# Power.net
KiCad netlist of a schematic drawn in Altium Designer
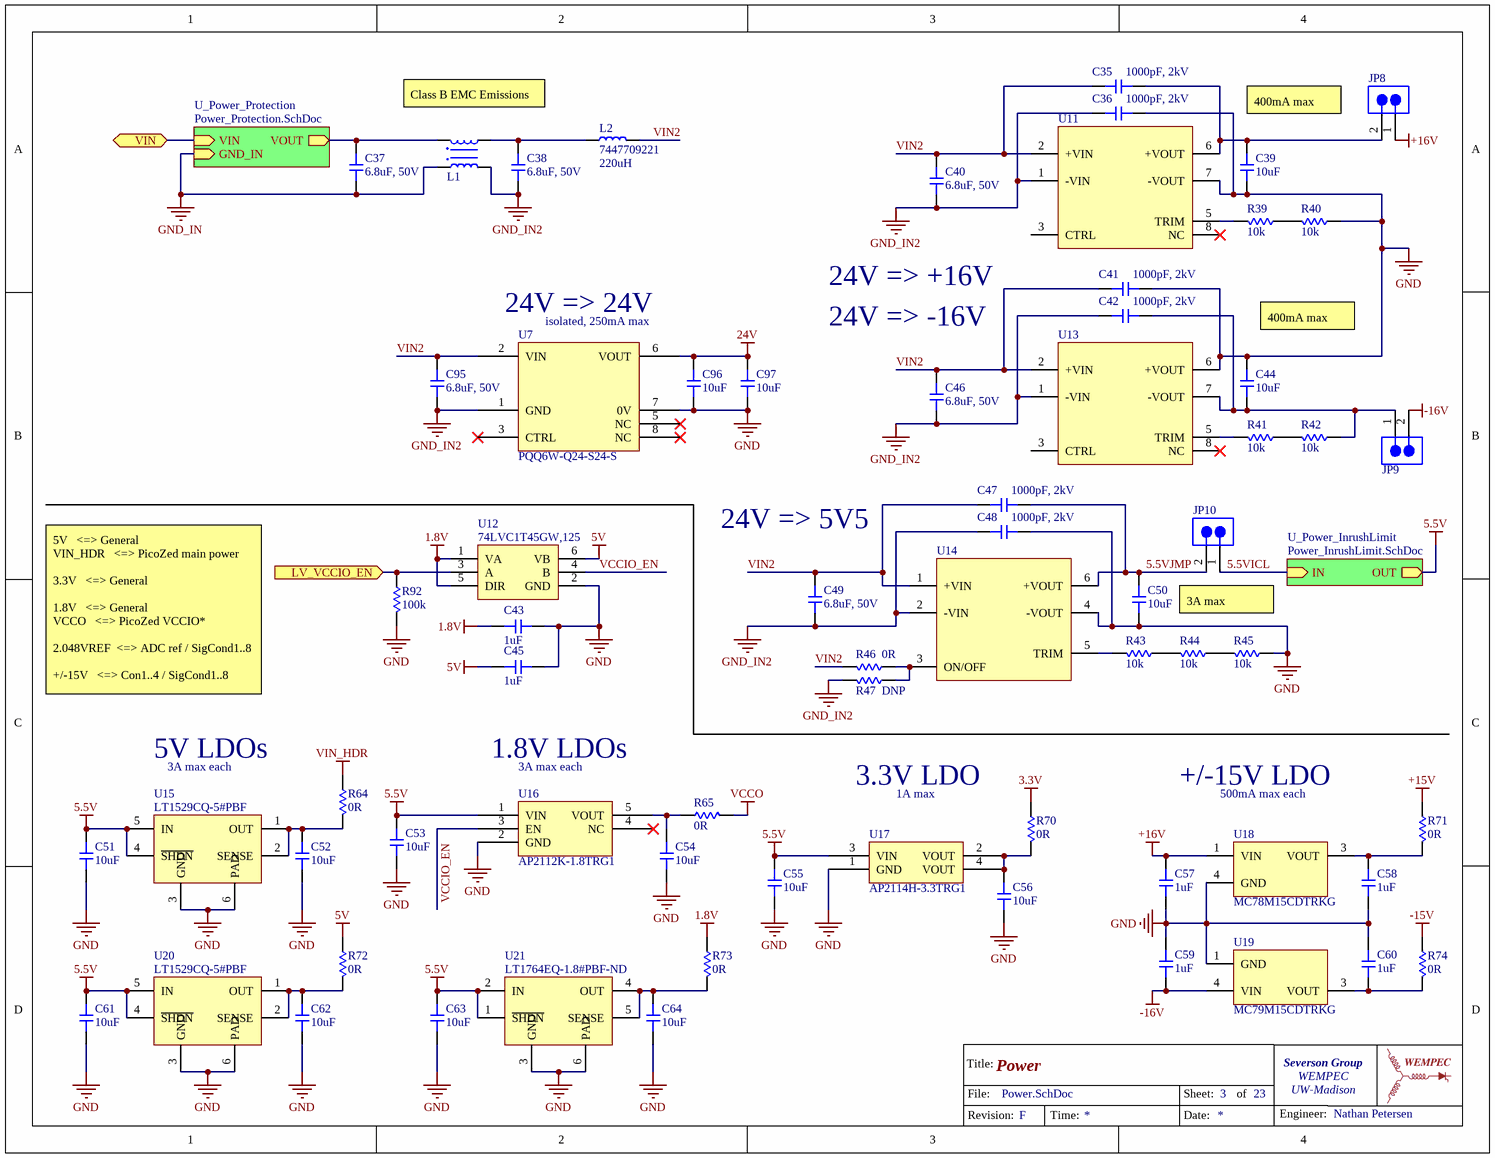
[diagram p0: Power.SchDoc]

(export (version "E")
  (design (tool "Eeschema 10.0.6"))
  (components
    (comp (ref "C35")
      (value "1000pF, 2kV")
      (footprint "1808-CAP")
      (description "Capacitor")
      (libsource (lib "AMDC") (part "Capacitor"))
    )
    (comp (ref "C36")
      (value "1000pF, 2kV")
      (footprint "1808-CAP")
      (description "Capacitor")
      (libsource (lib "AMDC") (part "Capacitor"))
    )
    (comp (ref "C37")
      (value "6.8uF, 50V")
      (footprint "1812-CAP")
      (description "Capacitor")
      (libsource (lib "AMDC") (part "Capacitor"))
    )
    (comp (ref "C38")
      (value "6.8uF, 50V")
      (footprint "1812-CAP")
      (description "Capacitor")
      (libsource (lib "AMDC") (part "Capacitor"))
    )
    (comp (ref "C39")
      (value "10uF")
      (footprint "0603-CAP")
      (description "Capacitor")
      (libsource (lib "AMDC") (part "Capacitor"))
    )
    (comp (ref "C40")
      (value "6.8uF, 50V")
      (footprint "1812-CAP")
      (description "Capacitor")
      (libsource (lib "AMDC") (part "Capacitor"))
    )
    (comp (ref "C41")
      (value "1000pF, 2kV")
      (footprint "1808-CAP")
      (description "Capacitor")
      (libsource (lib "AMDC") (part "Capacitor"))
    )
    (comp (ref "C42")
      (value "1000pF, 2kV")
      (footprint "1808-CAP")
      (description "Capacitor")
      (libsource (lib "AMDC") (part "Capacitor"))
    )
    (comp (ref "C43")
      (value "1uF")
      (footprint "0603-CAP")
      (description "Capacitor")
      (libsource (lib "AMDC") (part "Capacitor"))
    )
    (comp (ref "C44")
      (value "10uF")
      (footprint "0603-CAP")
      (description "Capacitor")
      (libsource (lib "AMDC") (part "Capacitor"))
    )
    (comp (ref "C45")
      (value "1uF")
      (footprint "0603-CAP")
      (description "Capacitor")
      (libsource (lib "AMDC") (part "Capacitor"))
    )
    (comp (ref "C46")
      (value "6.8uF, 50V")
      (footprint "1812-CAP")
      (description "Capacitor")
      (libsource (lib "AMDC") (part "Capacitor"))
    )
    (comp (ref "C47")
      (value "1000pF, 2kV")
      (footprint "1808-CAP")
      (description "Capacitor")
      (libsource (lib "AMDC") (part "Capacitor"))
    )
    (comp (ref "C48")
      (value "1000pF, 2kV")
      (footprint "1808-CAP")
      (description "Capacitor")
      (libsource (lib "AMDC") (part "Capacitor"))
    )
    (comp (ref "C49")
      (value "6.8uF, 50V")
      (footprint "1812-CAP")
      (description "Capacitor")
      (libsource (lib "AMDC") (part "Capacitor"))
    )
    (comp (ref "C50")
      (value "10uF")
      (footprint "0603-CAP")
      (description "Capacitor")
      (libsource (lib "AMDC") (part "Capacitor"))
    )
    (comp (ref "C51")
      (value "10uF")
      (footprint "0603-CAP")
      (description "Capacitor")
      (libsource (lib "AMDC") (part "Capacitor"))
    )
    (comp (ref "C52")
      (value "10uF")
      (footprint "0603-CAP")
      (description "Capacitor")
      (libsource (lib "AMDC") (part "Capacitor"))
    )
    (comp (ref "C53")
      (value "10uF")
      (footprint "0603-CAP")
      (description "Capacitor")
      (libsource (lib "AMDC") (part "Capacitor"))
    )
    (comp (ref "C54")
      (value "10uF")
      (footprint "0603-CAP")
      (description "Capacitor")
      (libsource (lib "AMDC") (part "Capacitor"))
    )
    (comp (ref "C55")
      (value "10uF")
      (footprint "0603-CAP")
      (description "Capacitor")
      (libsource (lib "AMDC") (part "Capacitor"))
    )
    (comp (ref "C56")
      (value "10uF")
      (footprint "0603-CAP")
      (description "Capacitor")
      (libsource (lib "AMDC") (part "Capacitor"))
    )
    (comp (ref "C57")
      (value "1uF")
      (footprint "0603-CAP")
      (description "Capacitor")
      (libsource (lib "AMDC") (part "Capacitor"))
    )
    (comp (ref "C58")
      (value "1uF")
      (footprint "0603-CAP")
      (description "Capacitor")
      (libsource (lib "AMDC") (part "Capacitor"))
    )
    (comp (ref "C59")
      (value "1uF")
      (footprint "0603-CAP")
      (description "Capacitor")
      (libsource (lib "AMDC") (part "Capacitor"))
    )
    (comp (ref "C60")
      (value "1uF")
      (footprint "0603-CAP")
      (description "Capacitor")
      (libsource (lib "AMDC") (part "Capacitor"))
    )
    (comp (ref "C61")
      (value "10uF")
      (footprint "0603-CAP")
      (description "Capacitor")
      (libsource (lib "AMDC") (part "Capacitor"))
    )
    (comp (ref "C62")
      (value "10uF")
      (footprint "0603-CAP")
      (description "Capacitor")
      (libsource (lib "AMDC") (part "Capacitor"))
    )
    (comp (ref "C63")
      (value "10uF")
      (footprint "0603-CAP")
      (description "Capacitor")
      (libsource (lib "AMDC") (part "Capacitor"))
    )
    (comp (ref "C64")
      (value "10uF")
      (footprint "0603-CAP")
      (description "Capacitor")
      (libsource (lib "AMDC") (part "Capacitor"))
    )
    (comp (ref "C95")
      (value "6.8uF, 50V")
      (footprint "1812-CAP")
      (description "Capacitor")
      (libsource (lib "AMDC") (part "Capacitor"))
    )
    (comp (ref "C96")
      (value "10uF")
      (footprint "0603-CAP")
      (description "Capacitor")
      (libsource (lib "AMDC") (part "Capacitor"))
    )
    (comp (ref "C97")
      (value "10uF")
      (footprint "0603-CAP")
      (description "Capacitor")
      (libsource (lib "AMDC") (part "Capacitor"))
    )
    (comp (ref "JP8")
      (value "Jumper2")
      (footprint "PIN_HEADER_1x2")
      (libsource (lib "AMDC") (part "Jumper2"))
    )
    (comp (ref "JP9")
      (value "Jumper2")
      (footprint "PIN_HEADER_1x2")
      (libsource (lib "AMDC") (part "Jumper2"))
    )
    (comp (ref "JP10")
      (value "Jumper2")
      (footprint "PIN_HEADER_1x2")
      (libsource (lib "AMDC") (part "Jumper2"))
    )
    (comp (ref "L1")
      (value "CMC  744273801")
      (footprint "CMC 744273801")
      (description "CMC 450UH 6.5A 2LN TH")
      (libsource (lib "AMDC") (part "CMC  744273801"))
    )
    (comp (ref "L2")
      (value "7447709221")
      (footprint "7447709221")
      (description "FIXED IND 220UH 1.8A 300 MOHM")
      (fields (field (name "ALTIUM_VALUE") "220uH"))
      (libsource (lib "AMDC") (part "7447709221"))
    )
    (comp (ref "R39")
      (value "10k")
      (footprint "0603-RES")
      (description "Resistor")
      (libsource (lib "AMDC") (part "Resistor"))
    )
    (comp (ref "R40")
      (value "10k")
      (footprint "0603-RES")
      (description "Resistor")
      (libsource (lib "AMDC") (part "Resistor"))
    )
    (comp (ref "R41")
      (value "10k")
      (footprint "0603-RES")
      (description "Resistor")
      (libsource (lib "AMDC") (part "Resistor"))
    )
    (comp (ref "R42")
      (value "10k")
      (footprint "0603-RES")
      (description "Resistor")
      (libsource (lib "AMDC") (part "Resistor"))
    )
    (comp (ref "R43")
      (value "10k")
      (footprint "0603-RES")
      (description "Resistor")
      (libsource (lib "AMDC") (part "Resistor"))
    )
    (comp (ref "R44")
      (value "10k")
      (footprint "0603-RES")
      (description "Resistor")
      (libsource (lib "AMDC") (part "Resistor"))
    )
    (comp (ref "R45")
      (value "10k")
      (footprint "0603-RES")
      (description "Resistor")
      (libsource (lib "AMDC") (part "Resistor"))
    )
    (comp (ref "R46")
      (value "0R")
      (footprint "1206-RES")
      (description "Resistor")
      (libsource (lib "AMDC") (part "Resistor"))
    )
    (comp (ref "R47")
      (value "DNP")
      (footprint "1206-RES")
      (description "Resistor")
      (libsource (lib "AMDC") (part "Resistor"))
    )
    (comp (ref "R64")
      (value "0R")
      (footprint "1206-RES")
      (description "Resistor")
      (libsource (lib "AMDC") (part "Resistor"))
    )
    (comp (ref "R65")
      (value "0R")
      (footprint "1206-RES")
      (description "Resistor")
      (libsource (lib "AMDC") (part "Resistor"))
    )
    (comp (ref "R70")
      (value "0R")
      (footprint "1206-RES")
      (description "Resistor")
      (libsource (lib "AMDC") (part "Resistor"))
    )
    (comp (ref "R71")
      (value "0R")
      (footprint "1206-RES")
      (description "Resistor")
      (libsource (lib "AMDC") (part "Resistor"))
    )
    (comp (ref "R72")
      (value "0R")
      (footprint "1206-RES")
      (description "Resistor")
      (libsource (lib "AMDC") (part "Resistor"))
    )
    (comp (ref "R73")
      (value "0R")
      (footprint "1206-RES")
      (description "Resistor")
      (libsource (lib "AMDC") (part "Resistor"))
    )
    (comp (ref "R74")
      (value "0R")
      (footprint "1206-RES")
      (description "Resistor")
      (libsource (lib "AMDC") (part "Resistor"))
    )
    (comp (ref "R92")
      (value "100k")
      (footprint "0603-RES")
      (description "Resistor")
      (libsource (lib "AMDC") (part "Resistor"))
    )
    (comp (ref "U7")
      (value "PQQ6W-Q24-S24-S")
      (footprint "PQQ6W-Q24-S24-S")
      (description "DC-DC ISOLATED, 6 W, 9~36 VDC IN")
      (libsource (lib "AMDC") (part "PQQ6W-Q24-S24-S"))
    )
    (comp (ref "U11")
      (value "DCDC Converter RS6")
      (footprint "RS6 DCDC")
      (description "Recom RS6")
      (libsource (lib "AMDC") (part "DCDC Converter RS6"))
    )
    (comp (ref "U12")
      (value "74LVC1T45GW,125")
      (footprint "SOT65P210X110-6N")
      (description "TXRX XLATING DUAL 3ST 6TSSOP")
      (libsource (lib "AMDC") (part "74LVC1T45GW,125"))
    )
    (comp (ref "U13")
      (value "DCDC Converter RS6")
      (footprint "RS6 DCDC")
      (description "Recom RS6")
      (libsource (lib "AMDC") (part "DCDC Converter RS6"))
    )
    (comp (ref "U14")
      (value "SHHD003A0A4Z")
      (footprint "DCDC SHHD003A0A41-SRZ")
      (description "DC DC CONVERTER 5V 15W")
      (libsource (lib "AMDC") (part "DCDC Converter SHHD003A0A41Z"))
    )
    (comp (ref "U15")
      (value "LT1529CQ-5#PBF")
      (footprint "5-DDPAK")
      (description "IC REG LINEAR 5V 3A 5DDPAK")
      (libsource (lib "AMDC") (part "LT1529CQ-5#PBF"))
    )
    (comp (ref "U16")
      (value "AP2112K-1.8TRG1")
      (footprint "SOT95P280X145-5N")
      (description "IC REG LINEAR 1.8V 600MA SOT25")
      (libsource (lib "AMDC") (part "AP2112K-1.8TRG1"))
    )
    (comp (ref "U17")
      (value "AP2114H-3.3TRG1")
      (footprint "SOT230P700X180-4N")
      (description "IC REG LINEAR 3.3V 1A SOT223")
      (libsource (lib "AMDC") (part "AP2114H-3.3TRG1"))
    )
    (comp (ref "U18")
      (value "MC78M15CDTRKG")
      (footprint "DPAK229P991X238-3N")
      (description "IC REG LINEAR 15V 500MA DPAK")
      (libsource (lib "AMDC") (part "MC78M15CDTRKG"))
    )
    (comp (ref "U19")
      (value "MC79M15CDTRKG")
      (footprint "DPAK229P991X238-3N")
      (description "IC REG LINEAR -15V 500MA DPAK")
      (libsource (lib "AMDC") (part "MC79M15CDTRKG"))
    )
    (comp (ref "U20")
      (value "LT1529CQ-5#PBF")
      (footprint "5-DDPAK")
      (description "IC REG LINEAR 5V 3A 5DDPAK")
      (libsource (lib "AMDC") (part "LT1529CQ-5#PBF"))
    )
    (comp (ref "U21")
      (value "LT1764EQ-1.8#PBF-ND")
      (footprint "5-DDPAK")
      (description "IC REG LINEAR 1.8V 3A 5DDPAK")
      (libsource (lib "AMDC") (part "LT1764EQ-1.8#PBF-ND"))
    )
  )
  (nets
    (net (code "1") (name "+15V") (class "Default")
      (node (ref "R71") (pin "1") (pinfunction "1_1") (pintype "passive"))
    )
    (net (code "2") (name "+16V") (class "Default")
      (node (ref "C57") (pin "2") (pinfunction "2_2") (pintype "passive"))
      (node (ref "JP8") (pin "1") (pinfunction "76_1") (pintype "passive"))
      (node (ref "U18") (pin "1") (pinfunction "VIN_1") (pintype "passive"))
    )
    (net (code "3") (name "-15V") (class "Default")
      (node (ref "R74") (pin "1") (pinfunction "1_1") (pintype "passive"))
    )
    (net (code "4") (name "-16V") (class "Default")
      (node (ref "C59") (pin "1") (pinfunction "1_1") (pintype "passive"))
      (node (ref "JP9") (pin "2") (pinfunction "75_2") (pintype "passive"))
      (node (ref "U19") (pin "4") (pinfunction "VIN_4") (pintype "passive"))
    )
    (net (code "5") (name "/5.5VICL") (class "Default")
      (node (ref "JP10") (pin "1") (pinfunction "76_1") (pintype "passive"))
    )
    (net (code "6") (name "/5.5VJMP") (class "Default")
      (node (ref "C47") (pin "2") (pinfunction "2_2") (pintype "passive"))
      (node (ref "C50") (pin "2") (pinfunction "2_2") (pintype "passive"))
      (node (ref "JP10") (pin "2") (pinfunction "75_2") (pintype "passive"))
      (node (ref "U14") (pin "6") (pinfunction "+VOUT_6") (pintype "passive"))
    )
    (net (code "7") (name "/LV_VCCIO_EN") (class "Default")
      (node (ref "R92") (pin "1") (pinfunction "1_1") (pintype "passive"))
      (node (ref "U12") (pin "3") (pinfunction "A_3") (pintype "passive"))
    )
    (net (code "8") (name "/VCCIO_EN") (class "Default")
      (node (ref "U12") (pin "4") (pinfunction "B_4") (pintype "passive"))
      (node (ref "U16") (pin "3") (pinfunction "EN_3") (pintype "passive"))
    )
    (net (code "10") (name "/VIN2") (class "Default")
      (node (ref "C35") (pin "1") (pinfunction "1_1") (pintype "passive"))
      (node (ref "C40") (pin "2") (pinfunction "2_2") (pintype "passive"))
      (node (ref "C41") (pin "1") (pinfunction "1_1") (pintype "passive"))
      (node (ref "C46") (pin "2") (pinfunction "2_2") (pintype "passive"))
      (node (ref "C47") (pin "1") (pinfunction "1_1") (pintype "passive"))
      (node (ref "C49") (pin "2") (pinfunction "2_2") (pintype "passive"))
      (node (ref "C95") (pin "2") (pinfunction "2_2") (pintype "passive"))
      (node (ref "L2") (pin "1") (pinfunction "1_1") (pintype "passive"))
      (node (ref "R46") (pin "2") (pinfunction "2_2") (pintype "passive"))
      (node (ref "U11") (pin "2") (pinfunction "+VIN_2") (pintype "passive"))
      (node (ref "U13") (pin "2") (pinfunction "+VIN_2") (pintype "passive"))
      (node (ref "U14") (pin "1") (pinfunction "+VIN_1") (pintype "passive"))
      (node (ref "U7") (pin "2") (pinfunction "VIN_2") (pintype "passive"))
    )
    (net (code "11") (name "/VOUT") (class "Default")
      (node (ref "C37") (pin "2") (pinfunction "2_2") (pintype "passive"))
      (node (ref "L1") (pin "1") (pinfunction "1_1") (pintype "passive"))
    )
    (net (code "12") (name "1.8V") (class "Default")
      (node (ref "C43") (pin "1") (pinfunction "1_1") (pintype "passive"))
      (node (ref "R73") (pin "1") (pinfunction "1_1") (pintype "passive"))
      (node (ref "U12") (pin "1") (pinfunction "VA_1") (pintype "passive"))
      (node (ref "U12") (pin "5") (pinfunction "DIR_5") (pintype "passive"))
    )
    (net (code "13") (name "3.3V") (class "Default")
      (node (ref "R70") (pin "1") (pinfunction "1_1") (pintype "passive"))
    )
    (net (code "14") (name "5.5V") (class "Default")
      (node (ref "C51") (pin "1") (pinfunction "1_1") (pintype "passive"))
      (node (ref "C53") (pin "1") (pinfunction "1_1") (pintype "passive"))
      (node (ref "C55") (pin "1") (pinfunction "1_1") (pintype "passive"))
      (node (ref "C61") (pin "1") (pinfunction "1_1") (pintype "passive"))
      (node (ref "C63") (pin "1") (pinfunction "1_1") (pintype "passive"))
      (node (ref "U15") (pin "4") (pinfunction "~{SHDN}_4") (pintype "passive"))
      (node (ref "U15") (pin "5") (pinfunction "IN_5") (pintype "passive"))
      (node (ref "U16") (pin "1") (pinfunction "VIN_1") (pintype "passive"))
      (node (ref "U17") (pin "3") (pinfunction "VIN_3") (pintype "passive"))
      (node (ref "U20") (pin "4") (pinfunction "~{SHDN}_4") (pintype "passive"))
      (node (ref "U20") (pin "5") (pinfunction "IN_5") (pintype "passive"))
      (node (ref "U21") (pin "1") (pinfunction "~{SHDN}_1") (pintype "passive"))
      (node (ref "U21") (pin "2") (pinfunction "IN_2") (pintype "passive"))
    )
    (net (code "15") (name "5V") (class "Default")
      (node (ref "C45") (pin "1") (pinfunction "1_1") (pintype "passive"))
      (node (ref "R72") (pin "1") (pinfunction "1_1") (pintype "passive"))
      (node (ref "U12") (pin "6") (pinfunction "VB_6") (pintype "passive"))
    )
    (net (code "16") (name "24V") (class "Default")
      (node (ref "C96") (pin "2") (pinfunction "2_2") (pintype "passive"))
      (node (ref "C97") (pin "2") (pinfunction "2_2") (pintype "passive"))
      (node (ref "U7") (pin "6") (pinfunction "VOUT_6") (pintype "passive"))
    )
    (net (code "17") (name "GND") (class "Default")
      (node (ref "C36") (pin "2") (pinfunction "2_2") (pintype "passive"))
      (node (ref "C39") (pin "1") (pinfunction "1_1") (pintype "passive"))
      (node (ref "C41") (pin "2") (pinfunction "2_2") (pintype "passive"))
      (node (ref "C43") (pin "2") (pinfunction "2_2") (pintype "passive"))
      (node (ref "C44") (pin "2") (pinfunction "2_2") (pintype "passive"))
      (node (ref "C45") (pin "2") (pinfunction "2_2") (pintype "passive"))
      (node (ref "C48") (pin "2") (pinfunction "2_2") (pintype "passive"))
      (node (ref "C50") (pin "1") (pinfunction "1_1") (pintype "passive"))
      (node (ref "C51") (pin "2") (pinfunction "2_2") (pintype "passive"))
      (node (ref "C52") (pin "2") (pinfunction "2_2") (pintype "passive"))
      (node (ref "C53") (pin "2") (pinfunction "2_2") (pintype "passive"))
      (node (ref "C54") (pin "2") (pinfunction "2_2") (pintype "passive"))
      (node (ref "C55") (pin "2") (pinfunction "2_2") (pintype "passive"))
      (node (ref "C56") (pin "2") (pinfunction "2_2") (pintype "passive"))
      (node (ref "C57") (pin "1") (pinfunction "1_1") (pintype "passive"))
      (node (ref "C58") (pin "1") (pinfunction "1_1") (pintype "passive"))
      (node (ref "C59") (pin "2") (pinfunction "2_2") (pintype "passive"))
      (node (ref "C60") (pin "2") (pinfunction "2_2") (pintype "passive"))
      (node (ref "C61") (pin "2") (pinfunction "2_2") (pintype "passive"))
      (node (ref "C62") (pin "2") (pinfunction "2_2") (pintype "passive"))
      (node (ref "C63") (pin "2") (pinfunction "2_2") (pintype "passive"))
      (node (ref "C64") (pin "2") (pinfunction "2_2") (pintype "passive"))
      (node (ref "C96") (pin "1") (pinfunction "1_1") (pintype "passive"))
      (node (ref "C97") (pin "1") (pinfunction "1_1") (pintype "passive"))
      (node (ref "R40") (pin "1") (pinfunction "1_1") (pintype "passive"))
      (node (ref "R45") (pin "1") (pinfunction "1_1") (pintype "passive"))
      (node (ref "R92") (pin "2") (pinfunction "2_2") (pintype "passive"))
      (node (ref "U11") (pin "7") (pinfunction "-VOUT_7") (pintype "passive"))
      (node (ref "U12") (pin "2") (pinfunction "GND_2") (pintype "passive"))
      (node (ref "U13") (pin "6") (pinfunction "+VOUT_6") (pintype "passive"))
      (node (ref "U14") (pin "4") (pinfunction "-VOUT_4") (pintype "passive"))
      (node (ref "U15") (pin "3") (pinfunction "GND_3") (pintype "passive"))
      (node (ref "U15") (pin "6") (pinfunction "PAD_6") (pintype "passive"))
      (node (ref "U16") (pin "2") (pinfunction "GND_2") (pintype "passive"))
      (node (ref "U17") (pin "1") (pinfunction "GND_1") (pintype "passive"))
      (node (ref "U18") (pin "4") (pinfunction "GND_4") (pintype "passive"))
      (node (ref "U19") (pin "1") (pinfunction "GND_1") (pintype "passive"))
      (node (ref "U20") (pin "3") (pinfunction "GND_3") (pintype "passive"))
      (node (ref "U20") (pin "6") (pinfunction "PAD_6") (pintype "passive"))
      (node (ref "U21") (pin "3") (pinfunction "GND_3") (pintype "passive"))
      (node (ref "U21") (pin "6") (pinfunction "PAD_6") (pintype "passive"))
      (node (ref "U7") (pin "7") (pinfunction "0V_7") (pintype "passive"))
    )
    (net (code "18") (name "GND_IN") (class "Default")
      (node (ref "C37") (pin "1") (pinfunction "1_1") (pintype "passive"))
      (node (ref "L1") (pin "2") (pinfunction "2_2") (pintype "passive"))
    )
    (net (code "19") (name "GND_IN2") (class "Default")
      (node (ref "C36") (pin "1") (pinfunction "1_1") (pintype "passive"))
      (node (ref "C38") (pin "1") (pinfunction "1_1") (pintype "passive"))
      (node (ref "C40") (pin "1") (pinfunction "1_1") (pintype "passive"))
      (node (ref "C42") (pin "1") (pinfunction "1_1") (pintype "passive"))
      (node (ref "C46") (pin "1") (pinfunction "1_1") (pintype "passive"))
      (node (ref "C48") (pin "1") (pinfunction "1_1") (pintype "passive"))
      (node (ref "C49") (pin "1") (pinfunction "1_1") (pintype "passive"))
      (node (ref "C95") (pin "1") (pinfunction "1_1") (pintype "passive"))
      (node (ref "L1") (pin "3") (pinfunction "3_3") (pintype "passive"))
      (node (ref "R47") (pin "2") (pinfunction "2_2") (pintype "passive"))
      (node (ref "U11") (pin "1") (pinfunction "-VIN_1") (pintype "passive"))
      (node (ref "U13") (pin "1") (pinfunction "-VIN_1") (pintype "passive"))
      (node (ref "U14") (pin "2") (pinfunction "-VIN_2") (pintype "passive"))
      (node (ref "U7") (pin "1") (pinfunction "GND_1") (pintype "passive"))
    )
    (net (code "20") (name "Net-(C38-Pad2)") (class "Default")
      (node (ref "C38") (pin "2") (pinfunction "2_2") (pintype "passive"))
      (node (ref "L1") (pin "4") (pinfunction "4_4") (pintype "passive"))
      (node (ref "L2") (pin "2") (pinfunction "2_2") (pintype "passive"))
    )
    (net (code "21") (name "Net-(C56-Pad1)") (class "Default")
      (node (ref "C56") (pin "1") (pinfunction "1_1") (pintype "passive"))
      (node (ref "R70") (pin "2") (pinfunction "2_2") (pintype "passive"))
      (node (ref "U17") (pin "2") (pinfunction "VOUT_2") (pintype "passive"))
      (node (ref "U17") (pin "4") (pinfunction "VOUT_4") (pintype "passive"))
    )
    (net (code "22") (name "Net-(JP8-75)") (class "Default")
      (node (ref "C35") (pin "2") (pinfunction "2_2") (pintype "passive"))
      (node (ref "C39") (pin "2") (pinfunction "2_2") (pintype "passive"))
      (node (ref "JP8") (pin "2") (pinfunction "75_2") (pintype "passive"))
      (node (ref "U11") (pin "6") (pinfunction "+VOUT_6") (pintype "passive"))
    )
    (net (code "23") (name "Net-(JP9-76)") (class "Default")
      (node (ref "C42") (pin "2") (pinfunction "2_2") (pintype "passive"))
      (node (ref "C44") (pin "1") (pinfunction "1_1") (pintype "passive"))
      (node (ref "JP9") (pin "1") (pinfunction "76_1") (pintype "passive"))
      (node (ref "R42") (pin "1") (pinfunction "1_1") (pintype "passive"))
      (node (ref "U13") (pin "7") (pinfunction "-VOUT_7") (pintype "passive"))
    )
    (net (code "24") (name "Net-(R39-Pad1)") (class "Default")
      (node (ref "R39") (pin "1") (pinfunction "1_1") (pintype "passive"))
      (node (ref "R40") (pin "2") (pinfunction "2_2") (pintype "passive"))
    )
    (net (code "25") (name "Net-(R41-Pad1)") (class "Default")
      (node (ref "R41") (pin "1") (pinfunction "1_1") (pintype "passive"))
      (node (ref "R42") (pin "2") (pinfunction "2_2") (pintype "passive"))
    )
    (net (code "26") (name "Net-(R43-Pad1)") (class "Default")
      (node (ref "R43") (pin "1") (pinfunction "1_1") (pintype "passive"))
      (node (ref "R44") (pin "2") (pinfunction "2_2") (pintype "passive"))
    )
    (net (code "27") (name "Net-(R44-Pad1)") (class "Default")
      (node (ref "R44") (pin "1") (pinfunction "1_1") (pintype "passive"))
      (node (ref "R45") (pin "2") (pinfunction "2_2") (pintype "passive"))
    )
    (net (code "28") (name "Net-(U11-TRIM)") (class "Default")
      (node (ref "R39") (pin "2") (pinfunction "2_2") (pintype "passive"))
      (node (ref "U11") (pin "5") (pinfunction "TRIM_5") (pintype "passive"))
    )
    (net (code "29") (name "Net-(U13-TRIM)") (class "Default")
      (node (ref "R41") (pin "2") (pinfunction "2_2") (pintype "passive"))
      (node (ref "U13") (pin "5") (pinfunction "TRIM_5") (pintype "passive"))
    )
    (net (code "30") (name "Net-(U14-ON{slash}OFF)") (class "Default")
      (node (ref "R46") (pin "1") (pinfunction "1_1") (pintype "passive"))
      (node (ref "R47") (pin "1") (pinfunction "1_1") (pintype "passive"))
      (node (ref "U14") (pin "3") (pinfunction "ON/OFF_3") (pintype "passive"))
    )
    (net (code "31") (name "Net-(U14-TRIM)") (class "Default")
      (node (ref "R43") (pin "2") (pinfunction "2_2") (pintype "passive"))
      (node (ref "U14") (pin "5") (pinfunction "TRIM_5") (pintype "passive"))
    )
    (net (code "32") (name "Net-(U15-OUT)") (class "Default")
      (node (ref "C52") (pin "1") (pinfunction "1_1") (pintype "passive"))
      (node (ref "R64") (pin "2") (pinfunction "2_2") (pintype "passive"))
      (node (ref "U15") (pin "1") (pinfunction "OUT_1") (pintype "passive"))
      (node (ref "U15") (pin "2") (pinfunction "SENSE_2") (pintype "passive"))
    )
    (net (code "33") (name "Net-(U16-VOUT)") (class "Default")
      (node (ref "C54") (pin "1") (pinfunction "1_1") (pintype "passive"))
      (node (ref "R65") (pin "1") (pinfunction "1_1") (pintype "passive"))
      (node (ref "U16") (pin "5") (pinfunction "VOUT_5") (pintype "passive"))
    )
    (net (code "34") (name "Net-(U18-VOUT)") (class "Default")
      (node (ref "C58") (pin "2") (pinfunction "2_2") (pintype "passive"))
      (node (ref "R71") (pin "2") (pinfunction "2_2") (pintype "passive"))
      (node (ref "U18") (pin "3") (pinfunction "VOUT_3") (pintype "passive"))
    )
    (net (code "35") (name "Net-(U19-VOUT)") (class "Default")
      (node (ref "C60") (pin "1") (pinfunction "1_1") (pintype "passive"))
      (node (ref "R74") (pin "2") (pinfunction "2_2") (pintype "passive"))
      (node (ref "U19") (pin "3") (pinfunction "VOUT_3") (pintype "passive"))
    )
    (net (code "36") (name "Net-(U20-OUT)") (class "Default")
      (node (ref "C62") (pin "1") (pinfunction "1_1") (pintype "passive"))
      (node (ref "R72") (pin "2") (pinfunction "2_2") (pintype "passive"))
      (node (ref "U20") (pin "1") (pinfunction "OUT_1") (pintype "passive"))
      (node (ref "U20") (pin "2") (pinfunction "SENSE_2") (pintype "passive"))
    )
    (net (code "37") (name "Net-(U21-OUT)") (class "Default")
      (node (ref "C64") (pin "1") (pinfunction "1_1") (pintype "passive"))
      (node (ref "R73") (pin "2") (pinfunction "2_2") (pintype "passive"))
      (node (ref "U21") (pin "4") (pinfunction "OUT_4") (pintype "passive"))
      (node (ref "U21") (pin "5") (pinfunction "SENSE_5") (pintype "passive"))
    )
    (net (code "38") (name "VCCO") (class "Default")
      (node (ref "R65") (pin "2") (pinfunction "2_2") (pintype "passive"))
    )
    (net (code "39") (name "VIN_HDR") (class "Default")
      (node (ref "R64") (pin "1") (pinfunction "1_1") (pintype "passive"))
    )
    (net (code "40") (name "unconnected-(U7-CTRL-Pad3)") (class "Default")
      (node (ref "U7") (pin "3") (pinfunction "CTRL_3") (pintype "passive+no_connect"))
    )
    (net (code "41") (name "unconnected-(U7-NC-Pad5)") (class "Default")
      (node (ref "U7") (pin "5") (pinfunction "NC_5") (pintype "passive+no_connect"))
    )
    (net (code "42") (name "unconnected-(U7-NC-Pad8)") (class "Default")
      (node (ref "U7") (pin "8") (pinfunction "NC_8") (pintype "passive+no_connect"))
    )
    (net (code "43") (name "unconnected-(U11-CTRL-Pad3)") (class "Default")
      (node (ref "U11") (pin "3") (pinfunction "CTRL_3") (pintype "passive"))
    )
    (net (code "44") (name "unconnected-(U11-NC-Pad8)") (class "Default")
      (node (ref "U11") (pin "8") (pinfunction "NC_8") (pintype "passive+no_connect"))
    )
    (net (code "45") (name "unconnected-(U13-CTRL-Pad3)") (class "Default")
      (node (ref "U13") (pin "3") (pinfunction "CTRL_3") (pintype "passive"))
    )
    (net (code "46") (name "unconnected-(U13-NC-Pad8)") (class "Default")
      (node (ref "U13") (pin "8") (pinfunction "NC_8") (pintype "passive+no_connect"))
    )
    (net (code "47") (name "unconnected-(U16-NC-Pad4)") (class "Default")
      (node (ref "U16") (pin "4") (pinfunction "NC_4") (pintype "passive+no_connect"))
    )
  )
)
